# arduinoPlus.net
KiCad netlist of a schematic drawn in EAGLE
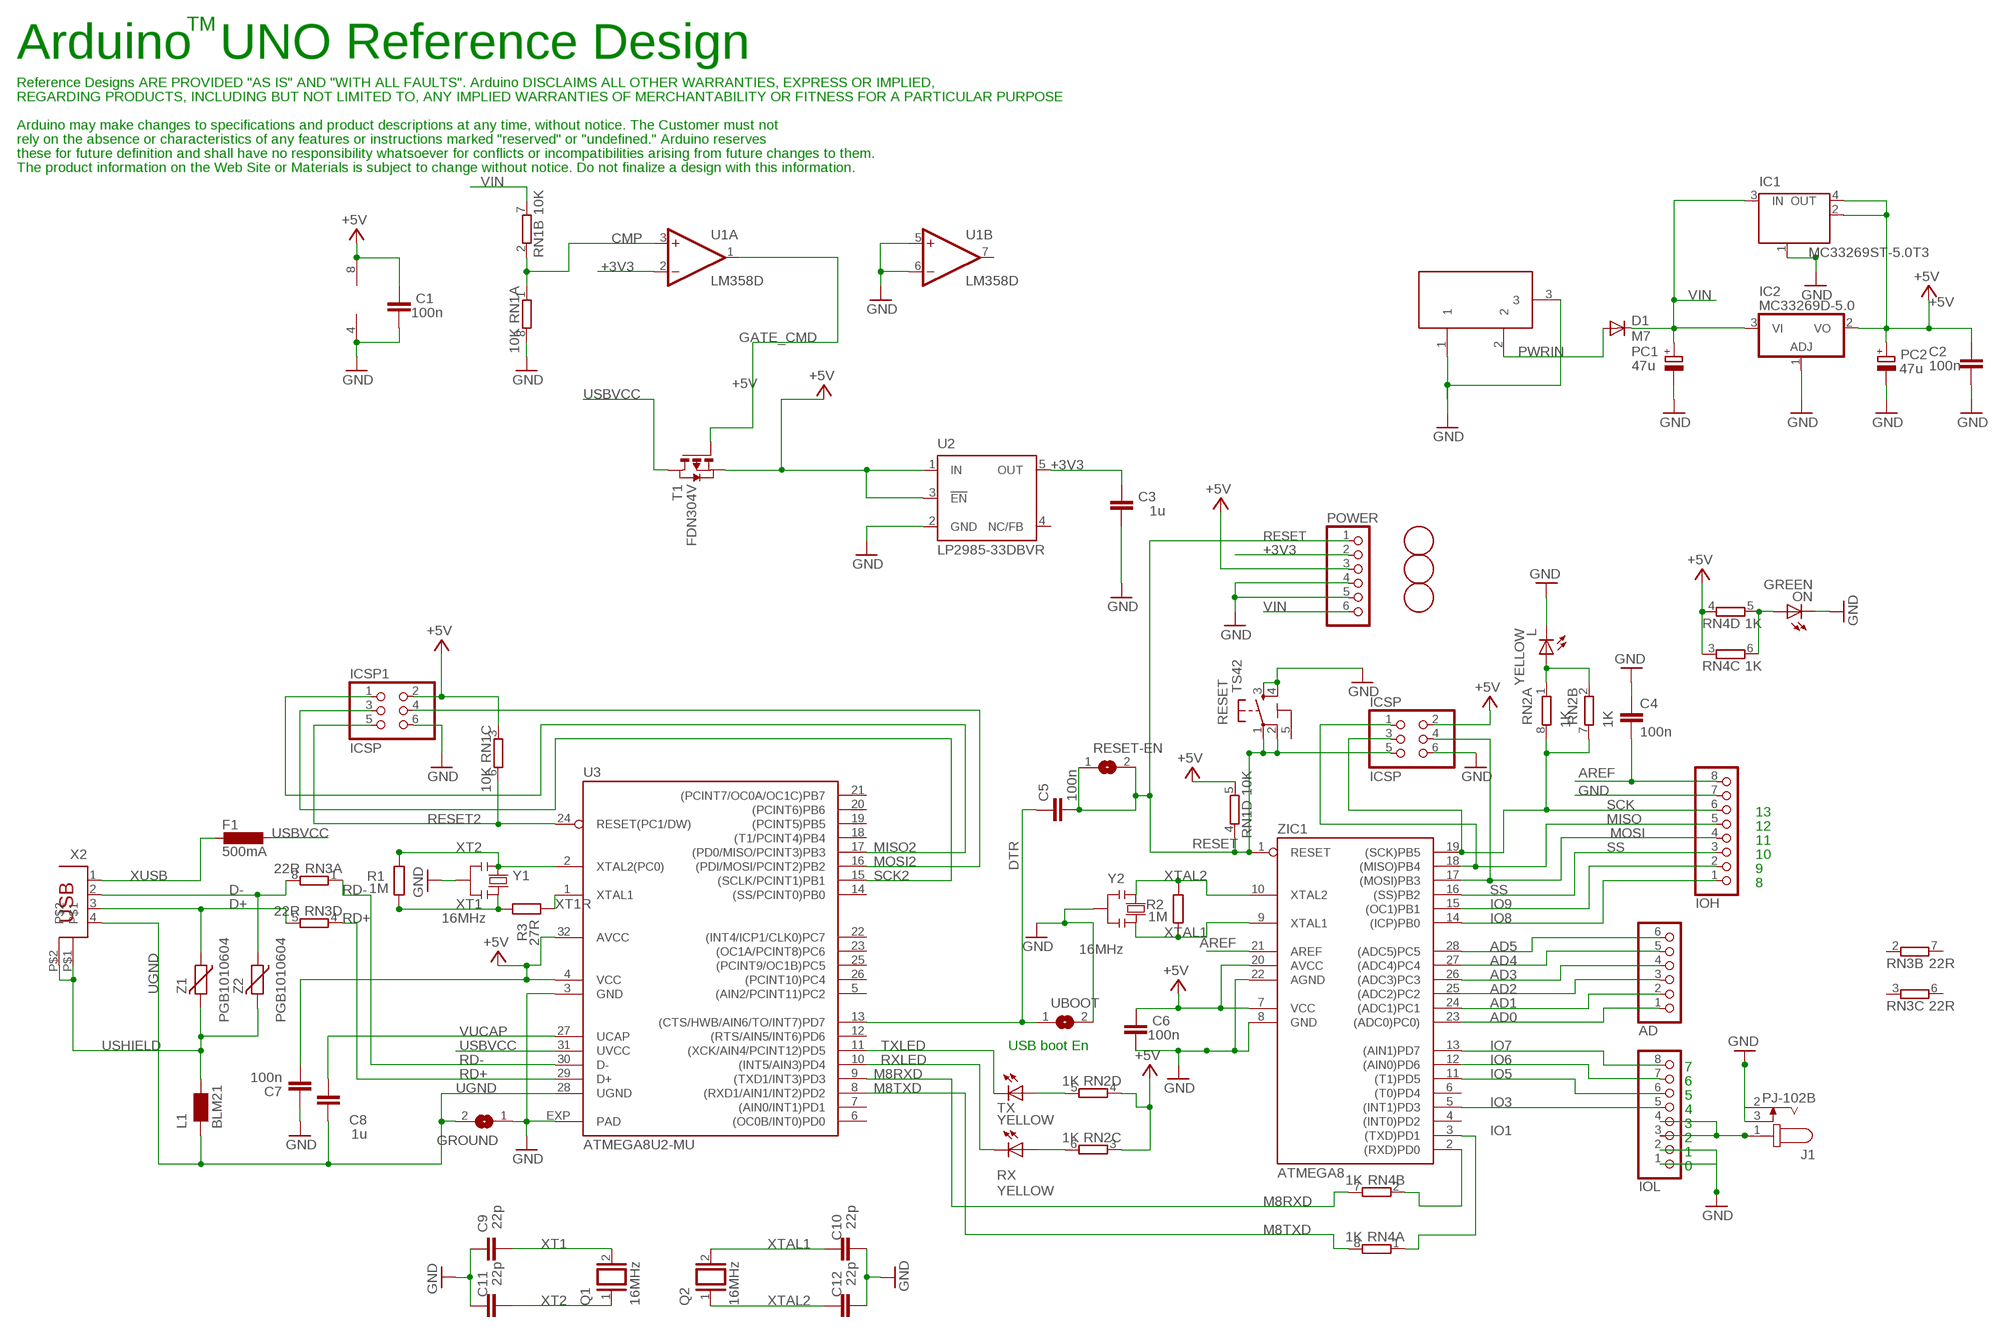
[diagram p0: schematic, sheet 1]

(export (version "E")
  (design (tool "Eeschema 10.0.6"))
  (components
    (comp (ref "AD")
      (value "PINHD-1X6")
      (footprint "eagle-import:1X06")
      (libsource (lib "eagle-import") (part "PINHD-1X6"))
    )
    (comp (ref "C1")
      (value "100n")
      (footprint "eagle-import:C0603-ROUND")
      (libsource (lib "eagle-import") (part "C-EU0603-RND"))
    )
    (comp (ref "C2")
      (value "100n")
      (footprint "eagle-import:C0603-ROUND")
      (libsource (lib "eagle-import") (part "C-EU0603-RND"))
    )
    (comp (ref "C3")
      (value "1u")
      (footprint "eagle-import:C0603-ROUND")
      (libsource (lib "eagle-import") (part "C-EU0603-RND"))
    )
    (comp (ref "C4")
      (value "100n")
      (footprint "eagle-import:C0603-ROUND")
      (libsource (lib "eagle-import") (part "C-EU0603-RND"))
    )
    (comp (ref "C5")
      (value "100n")
      (footprint "eagle-import:C0603-ROUND")
      (libsource (lib "eagle-import") (part "C-EU0603-RND"))
    )
    (comp (ref "C6")
      (value "100n")
      (footprint "eagle-import:C0603-ROUND")
      (libsource (lib "eagle-import") (part "C-EU0603-RND"))
    )
    (comp (ref "C7")
      (value "100n")
      (footprint "eagle-import:C0603-ROUND")
      (libsource (lib "eagle-import") (part "C-EU0603-RND"))
    )
    (comp (ref "C8")
      (value "1u")
      (footprint "eagle-import:C0603-ROUND")
      (libsource (lib "eagle-import") (part "C-EU0603-RND"))
    )
    (comp (ref "C9")
      (value "22p")
      (footprint "eagle-import:C0603-ROUND")
      (libsource (lib "eagle-import") (part "C-EU0603-RND"))
    )
    (comp (ref "C10")
      (value "22p")
      (footprint "eagle-import:C0603-ROUND")
      (libsource (lib "eagle-import") (part "C-EU0603-RND"))
    )
    (comp (ref "C11")
      (value "22p")
      (footprint "eagle-import:C0603-ROUND")
      (libsource (lib "eagle-import") (part "C-EU0603-RND"))
    )
    (comp (ref "C12")
      (value "22p")
      (footprint "eagle-import:C0603-ROUND")
      (libsource (lib "eagle-import") (part "C-EU0603-RND"))
    )
    (comp (ref "D1")
      (value "M7")
      (footprint "eagle-import:SMB")
      (libsource (lib "eagle-import") (part "DIODE-SMB"))
    )
    (comp (ref "F1")
      (value "500mA")
      (footprint "eagle-import:L1812")
      (libsource (lib "eagle-import") (part "L-EUL1812"))
    )
    (comp (ref "GROUND")
      (value "SJ")
      (footprint "eagle-import:SJ")
      (libsource (lib "eagle-import") (part "SJ"))
    )
    (comp (ref "IC1")
      (value "MC33269ST-5.0T3")
      (footprint "eagle-import:SOT223")
      (libsource (lib "eagle-import") (part "MC33269ST-3.3T3"))
    )
    (comp (ref "IC2")
      (value "MC33269D-5.0")
      (footprint "eagle-import:DPACK")
      (libsource (lib "eagle-import") (part "MC33269?D-5.0"))
    )
    (comp (ref "ICSP")
      (value "ICSP")
      (footprint "eagle-import:2X03")
      (libsource (lib "eagle-import") (part "PINHD-2X3"))
    )
    (comp (ref "ICSP1")
      (value "ICSP")
      (footprint "eagle-import:2X03")
      (libsource (lib "eagle-import") (part "PINHD-2X3"))
    )
    (comp (ref "IOH")
      (value "PINHD-1X8")
      (footprint "eagle-import:1X08")
      (libsource (lib "eagle-import") (part "PINHD-1X8"))
    )
    (comp (ref "IOL")
      (value "PINHD-1X8")
      (footprint "eagle-import:1X08")
      (libsource (lib "eagle-import") (part "PINHD-1X8"))
    )
    (comp (ref "J1")
      (value "PJ-102B")
      (footprint "eagle-import:CUI_PJ-102B")
      (fields (field (name "MF") "CUI Devices"))
      (libsource (lib "eagle-import") (part "PJ-102B"))
    )
    (comp (ref "L")
      (value "YELLOW")
      (footprint "eagle-import:CHIP-LED0805")
      (libsource (lib "eagle-import") (part "LEDCHIP-LED0805"))
    )
    (comp (ref "L1")
      (value "BLM21")
      (footprint "eagle-import:0805")
      (libsource (lib "eagle-import") (part "WE-CBF_0805"))
    )
    (comp (ref "ON")
      (value "GREEN")
      (footprint "eagle-import:CHIP-LED0805")
      (libsource (lib "eagle-import") (part "LEDCHIP-LED0805"))
    )
    (comp (ref "PC1")
      (value "47u")
      (footprint "eagle-import:PANASONIC_D")
      (libsource (lib "eagle-import") (part "CPOL-EUD"))
    )
    (comp (ref "PC2")
      (value "47u")
      (footprint "eagle-import:PANASONIC_D")
      (libsource (lib "eagle-import") (part "CPOL-EUD"))
    )
    (comp (ref "POWER")
      (value "PINHD-1X6")
      (footprint "eagle-import:1X06")
      (libsource (lib "eagle-import") (part "PINHD-1X6"))
    )
    (comp (ref "Q1")
      (value "16MHz")
      (footprint "eagle-import:QS")
      (libsource (lib "eagle-import") (part "XTAL/S"))
    )
    (comp (ref "Q2")
      (value "16MHz")
      (footprint "eagle-import:QS")
      (libsource (lib "eagle-import") (part "XTAL/S"))
    )
    (comp (ref "R1")
      (value "1M")
      (footprint "eagle-import:R0603-ROUND")
      (libsource (lib "eagle-import") (part "R-EU_R0603"))
    )
    (comp (ref "R2")
      (value "1M")
      (footprint "eagle-import:R0603-ROUND")
      (libsource (lib "eagle-import") (part "R-EU_R0603"))
    )
    (comp (ref "R3")
      (value "27R")
      (footprint "eagle-import:R0603-ROUND")
      (libsource (lib "eagle-import") (part "R-EU_R0603"))
    )
    (comp (ref "RESET")
      (value "TS42")
      (footprint "eagle-import:TS42")
      (libsource (lib "eagle-import") (part "TS42"))
    )
    (comp (ref "RESET-EN")
      (value "SJ")
      (footprint "eagle-import:SJ")
      (libsource (lib "eagle-import") (part "SJ"))
    )
    (comp (ref "RN1")
      (value "10K")
      (footprint "eagle-import:CAY16")
      (libsource (lib "eagle-import") (part "4R-NCAY16"))
    )
    (comp (ref "RN2")
      (value "1K")
      (footprint "eagle-import:CAY16")
      (libsource (lib "eagle-import") (part "4R-NCAY16"))
    )
    (comp (ref "RN3")
      (value "22R")
      (footprint "eagle-import:CAY16")
      (libsource (lib "eagle-import") (part "4R-NCAY16"))
    )
    (comp (ref "RN4")
      (value "1K")
      (footprint "eagle-import:CAY16")
      (libsource (lib "eagle-import") (part "4R-NCAY16"))
    )
    (comp (ref "RX")
      (value "YELLOW")
      (footprint "eagle-import:CHIP-LED0805")
      (libsource (lib "eagle-import") (part "LEDCHIP-LED0805"))
    )
    (comp (ref "T1")
      (value "FDN304V")
      (footprint "eagle-import:SOT-23")
      (libsource (lib "eagle-import") (part "PMOSSOT23"))
    )
    (comp (ref "TX")
      (value "YELLOW")
      (footprint "eagle-import:CHIP-LED0805")
      (libsource (lib "eagle-import") (part "LEDCHIP-LED0805"))
    )
    (comp (ref "U$3")
      (value "FIDUCIALMOUNT")
      (footprint "eagle-import:FIDUCIA-MOUNT")
      (libsource (lib "eagle-import") (part "FIDUCIALMOUNT"))
    )
    (comp (ref "U$4")
      (value "FIDUCIALMOUNT")
      (footprint "eagle-import:FIDUCIA-MOUNT")
      (libsource (lib "eagle-import") (part "FIDUCIALMOUNT"))
    )
    (comp (ref "U$6")
      (value "FIDUCIALMOUNT")
      (footprint "eagle-import:FIDUCIA-MOUNT")
      (libsource (lib "eagle-import") (part "FIDUCIALMOUNT"))
    )
    (comp (ref "U1")
      (value "LM358D")
      (footprint "eagle-import:SO08")
      (libsource (lib "eagle-import") (part "LM358D"))
    )
    (comp (ref "U2")
      (value "LP2985-33DBVR")
      (footprint "eagle-import:SOT23-DBV")
      (libsource (lib "eagle-import") (part "TPS77033"))
    )
    (comp (ref "U3")
      (value "ATMEGA8U2-MU")
      (footprint "eagle-import:QFN32")
      (libsource (lib "eagle-import") (part "ATMEGA8U2-MU"))
    )
    (comp (ref "UBOOT")
      (value "SJ")
      (footprint "eagle-import:SJ")
      (libsource (lib "eagle-import") (part "SJ"))
    )
    (comp (ref "X1")
      (value "DC21MMX")
      (footprint "eagle-import:DC-21MM")
      (libsource (lib "eagle-import") (part "DC21MMX"))
    )
    (comp (ref "X2")
      (value "PN61729")
      (footprint "eagle-import:PN61729")
      (libsource (lib "eagle-import") (part "PN61729"))
    )
    (comp (ref "Y1")
      (value "16MHz")
      (footprint "eagle-import:RESONATOR")
      (libsource (lib "eagle-import") (part "RESONATORMU"))
    )
    (comp (ref "Y2")
      (value "16MHz")
      (footprint "eagle-import:RESONATOR")
      (libsource (lib "eagle-import") (part "RESONATORMU"))
    )
    (comp (ref "Z1")
      (value "PGB1010604")
      (footprint "eagle-import:CT_CN0603")
      (libsource (lib "eagle-import") (part "VARISTORCN0603"))
    )
    (comp (ref "Z2")
      (value "PGB1010604")
      (footprint "eagle-import:CT_CN0603")
      (libsource (lib "eagle-import") (part "VARISTORCN0603"))
    )
    (comp (ref "ZIC1")
      (value "ATMEGA8")
      (footprint "eagle-import:DIL28-3")
      (libsource (lib "eagle-import") (part "AT90S4433P"))
    )
  )
  (nets
    (net (code "1") (name "+5V") (class "Default")
      (node (ref "C1") (pin "2") (pinfunction "2_2") (pintype "passive"))
      (node (ref "C2") (pin "2") (pinfunction "2_2") (pintype "passive"))
      (node (ref "C6") (pin "2") (pinfunction "2_2") (pintype "passive"))
      (node (ref "C7") (pin "1") (pinfunction "1_1") (pintype "passive"))
      (node (ref "IC1") (pin "2") (pinfunction "OUT_2") (pintype "passive"))
      (node (ref "IC1") (pin "4") (pinfunction "OUT_4") (pintype "passive"))
      (node (ref "IC2") (pin "2") (pinfunction "VO_2") (pintype "passive"))
      (node (ref "ICSP") (pin "2") (pinfunction "2_2") (pintype "passive"))
      (node (ref "ICSP1") (pin "2") (pinfunction "2_2") (pintype "passive"))
      (node (ref "PC2") (pin "+") (pinfunction "+_+") (pintype "passive"))
      (node (ref "POWER") (pin "3") (pinfunction "3_3") (pintype "passive"))
      (node (ref "RN1") (pin "3") (pinfunction "1_3") (pintype "passive"))
      (node (ref "RN1") (pin "5") (pinfunction "2_5") (pintype "passive"))
      (node (ref "RN2") (pin "3") (pinfunction "1_3") (pintype "passive"))
      (node (ref "RN2") (pin "4") (pinfunction "1_4") (pintype "passive"))
      (node (ref "RN4") (pin "3") (pinfunction "1_3") (pintype "passive"))
      (node (ref "RN4") (pin "4") (pinfunction "1_4") (pintype "passive"))
      (node (ref "T1") (pin "2") (pinfunction "S_2") (pintype "passive"))
      (node (ref "U1") (pin "8") (pinfunction "V+_8") (pintype "power_in"))
      (node (ref "U2") (pin "1") (pinfunction "IN_1") (pintype "input"))
      (node (ref "U2") (pin "3") (pinfunction "~{EN}_3") (pintype "input"))
      (node (ref "U3") (pin "32") (pinfunction "AVCC_32") (pintype "power_in"))
      (node (ref "U3") (pin "4") (pinfunction "VCC_4") (pintype "power_in"))
      (node (ref "ZIC1") (pin "20") (pinfunction "AVCC_20") (pintype "power_in"))
      (node (ref "ZIC1") (pin "7") (pinfunction "VCC_7") (pintype "power_in"))
    )
    (net (code "2") (name "/+3V3") (class "Default")
      (node (ref "C3") (pin "2") (pinfunction "2_2") (pintype "passive"))
      (node (ref "POWER") (pin "2") (pinfunction "2_2") (pintype "passive"))
      (node (ref "U1") (pin "2") (pinfunction "-IN_2") (pintype "input"))
      (node (ref "U2") (pin "5") (pinfunction "OUT_5") (pintype "passive"))
    )
    (net (code "3") (name "/5-GND") (class "Default")
      (node (ref "RESET") (pin "5") (pinfunction "5-GND_5") (pintype "power_in"))
    )
    (net (code "4") (name "/AD0") (class "Default")
      (node (ref "AD") (pin "1") (pinfunction "1_1") (pintype "passive"))
      (node (ref "ZIC1") (pin "23") (pinfunction "(ADC0)PC0)_23") (pintype "bidirectional"))
    )
    (net (code "5") (name "/AD1") (class "Default")
      (node (ref "AD") (pin "2") (pinfunction "2_2") (pintype "passive"))
      (node (ref "ZIC1") (pin "24") (pinfunction "(ADC1)PC1_24") (pintype "bidirectional"))
    )
    (net (code "6") (name "/AD2") (class "Default")
      (node (ref "AD") (pin "3") (pinfunction "3_3") (pintype "passive"))
      (node (ref "ZIC1") (pin "25") (pinfunction "(ADC2)PC2_25") (pintype "bidirectional"))
    )
    (net (code "7") (name "/AD3") (class "Default")
      (node (ref "AD") (pin "4") (pinfunction "4_4") (pintype "passive"))
      (node (ref "ZIC1") (pin "26") (pinfunction "(ADC3)PC3_26") (pintype "bidirectional"))
    )
    (net (code "8") (name "/AD4") (class "Default")
      (node (ref "AD") (pin "5") (pinfunction "5_5") (pintype "passive"))
      (node (ref "ZIC1") (pin "27") (pinfunction "(ADC4)PC4_27") (pintype "bidirectional"))
    )
    (net (code "9") (name "/AD5") (class "Default")
      (node (ref "AD") (pin "6") (pinfunction "6_6") (pintype "passive"))
      (node (ref "ZIC1") (pin "28") (pinfunction "(ADC5)PC5_28") (pintype "bidirectional"))
    )
    (net (code "10") (name "/AREF") (class "Default")
      (node (ref "C4") (pin "2") (pinfunction "2_2") (pintype "passive"))
      (node (ref "IOH") (pin "8") (pinfunction "8_8") (pintype "passive"))
      (node (ref "ZIC1") (pin "21") (pinfunction "AREF_21") (pintype "passive"))
    )
    (net (code "11") (name "/CMP") (class "Default")
      (node (ref "RN1") (pin "1") (pinfunction "1_1") (pintype "passive"))
      (node (ref "RN1") (pin "2") (pinfunction "1_2") (pintype "passive"))
      (node (ref "U1") (pin "3") (pinfunction "+IN_3") (pintype "input"))
    )
    (net (code "12") (name "/D+") (class "Default")
      (node (ref "RN3") (pin "5") (pinfunction "2_5") (pintype "passive"))
      (node (ref "X2") (pin "3") (pinfunction "3_3") (pintype "bidirectional"))
      (node (ref "Z1") (pin "1") (pinfunction "1_1") (pintype "passive"))
    )
    (net (code "13") (name "/D-") (class "Default")
      (node (ref "RN3") (pin "8") (pinfunction "2_8") (pintype "passive"))
      (node (ref "X2") (pin "2") (pinfunction "2_2") (pintype "bidirectional"))
      (node (ref "Z2") (pin "1") (pinfunction "1_1") (pintype "passive"))
    )
    (net (code "14") (name "/DTR") (class "Default")
      (node (ref "C5") (pin "1") (pinfunction "1_1") (pintype "passive"))
      (node (ref "U3") (pin "13") (pinfunction "(CTS/HWB/AIN6/TO/INT7)PD7_13") (pintype "bidirectional"))
      (node (ref "UBOOT") (pin "1") (pinfunction "1_1") (pintype "passive"))
    )
    (net (code "15") (name "/GATE_CMD") (class "Default")
      (node (ref "T1") (pin "3") (pinfunction "G_3") (pintype "passive"))
      (node (ref "U1") (pin "1") (pinfunction "OUT_1") (pintype "output"))
    )
    (net (code "16") (name "/IO1") (class "Default")
      (node (ref "RN4") (pin "1") (pinfunction "1_1") (pintype "passive"))
      (node (ref "ZIC1") (pin "3") (pinfunction "(TXD)PD1_3") (pintype "bidirectional"))
    )
    (net (code "17") (name "/IO3") (class "Default")
      (node (ref "IOL") (pin "5") (pinfunction "5_5") (pintype "passive"))
      (node (ref "ZIC1") (pin "5") (pinfunction "(INT1)PD3_5") (pintype "bidirectional"))
    )
    (net (code "18") (name "/IO5") (class "Default")
      (node (ref "IOL") (pin "6") (pinfunction "6_6") (pintype "passive"))
      (node (ref "ZIC1") (pin "11") (pinfunction "(T1)PD5_11") (pintype "bidirectional"))
    )
    (net (code "19") (name "/IO6") (class "Default")
      (node (ref "IOL") (pin "7") (pinfunction "7_7") (pintype "passive"))
      (node (ref "ZIC1") (pin "12") (pinfunction "(AIN0)PD6_12") (pintype "bidirectional"))
    )
    (net (code "20") (name "/IO7") (class "Default")
      (node (ref "IOL") (pin "8") (pinfunction "8_8") (pintype "passive"))
      (node (ref "ZIC1") (pin "13") (pinfunction "(AIN1)PD7_13") (pintype "bidirectional"))
    )
    (net (code "21") (name "/IO8") (class "Default")
      (node (ref "IOH") (pin "1") (pinfunction "1_1") (pintype "passive"))
      (node (ref "ZIC1") (pin "14") (pinfunction "(ICP)PB0_14") (pintype "bidirectional"))
    )
    (net (code "22") (name "/IO9") (class "Default")
      (node (ref "IOH") (pin "2") (pinfunction "2_2") (pintype "passive"))
      (node (ref "ZIC1") (pin "15") (pinfunction "(OC1)PB1_15") (pintype "bidirectional"))
    )
    (net (code "23") (name "/M8RXD") (class "Default")
      (node (ref "RN4") (pin "7") (pinfunction "2_7") (pintype "passive"))
      (node (ref "U3") (pin "9") (pinfunction "(TXD1/INT3)PD3_9") (pintype "bidirectional"))
    )
    (net (code "24") (name "/M8TXD") (class "Default")
      (node (ref "RN4") (pin "8") (pinfunction "2_8") (pintype "passive"))
      (node (ref "U3") (pin "8") (pinfunction "(RXD1/AIN1/INT2)PD2_8") (pintype "bidirectional"))
    )
    (net (code "25") (name "/MISO") (class "Default")
      (node (ref "ICSP") (pin "1") (pinfunction "1_1") (pintype "passive"))
      (node (ref "IOH") (pin "5") (pinfunction "5_5") (pintype "passive"))
      (node (ref "ZIC1") (pin "18") (pinfunction "(MISO)PB4_18") (pintype "bidirectional"))
    )
    (net (code "26") (name "/MISO2") (class "Default")
      (node (ref "ICSP1") (pin "1") (pinfunction "1_1") (pintype "passive"))
      (node (ref "U3") (pin "17") (pinfunction "(PD0/MISO/PCINT3)PB3_17") (pintype "bidirectional"))
    )
    (net (code "27") (name "/MOSI") (class "Default")
      (node (ref "ICSP") (pin "4") (pinfunction "4_4") (pintype "passive"))
      (node (ref "IOH") (pin "4") (pinfunction "4_4") (pintype "passive"))
      (node (ref "ZIC1") (pin "17") (pinfunction "(MOSI)PB3_17") (pintype "bidirectional"))
    )
    (net (code "28") (name "/MOSI2") (class "Default")
      (node (ref "ICSP1") (pin "4") (pinfunction "4_4") (pintype "passive"))
      (node (ref "U3") (pin "16") (pinfunction "(PDI/MOSI/PCINT2)PB2_16") (pintype "bidirectional"))
    )
    (net (code "29") (name "/PWRIN") (class "Default")
      (node (ref "D1") (pin "A") (pinfunction "A_A") (pintype "passive"))
      (node (ref "X1") (pin "2") (pinfunction "2_2") (pintype "power_in"))
    )
    (net (code "30") (name "/RD+") (class "Default")
      (node (ref "RN3") (pin "4") (pinfunction "1_4") (pintype "passive"))
      (node (ref "U3") (pin "29") (pinfunction "D+_29") (pintype "bidirectional"))
    )
    (net (code "31") (name "/RD-") (class "Default")
      (node (ref "RN3") (pin "1") (pinfunction "1_1") (pintype "passive"))
      (node (ref "U3") (pin "30") (pinfunction "D-_30") (pintype "bidirectional"))
    )
    (net (code "32") (name "/RESET") (class "Default")
      (node (ref "C5") (pin "2") (pinfunction "2_2") (pintype "passive"))
      (node (ref "ICSP") (pin "5") (pinfunction "5_5") (pintype "passive"))
      (node (ref "POWER") (pin "1") (pinfunction "1_1") (pintype "passive"))
      (node (ref "RESET") (pin "1") (pinfunction "1_1") (pintype "passive"))
      (node (ref "RESET") (pin "2") (pinfunction "2_2") (pintype "passive"))
      (node (ref "RESET-EN") (pin "1") (pinfunction "1_1") (pintype "passive"))
      (node (ref "RESET-EN") (pin "2") (pinfunction "2_2") (pintype "passive"))
      (node (ref "RN1") (pin "4") (pinfunction "1_4") (pintype "passive"))
      (node (ref "ZIC1") (pin "1") (pinfunction "RESET_1") (pintype "input"))
    )
    (net (code "33") (name "/RESET2") (class "Default")
      (node (ref "ICSP1") (pin "5") (pinfunction "5_5") (pintype "passive"))
      (node (ref "RN1") (pin "6") (pinfunction "2_6") (pintype "passive"))
      (node (ref "U3") (pin "24") (pinfunction "RESET(PC1/DW)_24") (pintype "input"))
    )
    (net (code "34") (name "/RXLED") (class "Default")
      (node (ref "RX") (pin "C") (pinfunction "C_C") (pintype "passive"))
      (node (ref "U3") (pin "10") (pinfunction "(INT5/AIN3)PD4_10") (pintype "bidirectional"))
    )
    (net (code "35") (name "/SCK") (class "Default")
      (node (ref "ICSP") (pin "3") (pinfunction "3_3") (pintype "passive"))
      (node (ref "IOH") (pin "6") (pinfunction "6_6") (pintype "passive"))
      (node (ref "RN2") (pin "7") (pinfunction "2_7") (pintype "passive"))
      (node (ref "RN2") (pin "8") (pinfunction "2_8") (pintype "passive"))
      (node (ref "ZIC1") (pin "19") (pinfunction "(SCK)PB5_19") (pintype "bidirectional"))
    )
    (net (code "36") (name "/SCK2") (class "Default")
      (node (ref "ICSP1") (pin "3") (pinfunction "3_3") (pintype "passive"))
      (node (ref "U3") (pin "15") (pinfunction "(SCLK/PCINT1)PB1_15") (pintype "bidirectional"))
    )
    (net (code "37") (name "/SS") (class "Default")
      (node (ref "IOH") (pin "3") (pinfunction "3_3") (pintype "passive"))
      (node (ref "ZIC1") (pin "16") (pinfunction "(SS)PB2_16") (pintype "bidirectional"))
    )
    (net (code "38") (name "/TXLED") (class "Default")
      (node (ref "TX") (pin "C") (pinfunction "C_C") (pintype "passive"))
      (node (ref "U3") (pin "11") (pinfunction "(XCK/AIN4/PCINT12)PD5_11") (pintype "bidirectional"))
    )
    (net (code "39") (name "/UGND") (class "Default")
      (node (ref "C8") (pin "2") (pinfunction "2_2") (pintype "passive"))
      (node (ref "GROUND") (pin "2") (pinfunction "2_2") (pintype "passive"))
      (node (ref "L1") (pin "1") (pinfunction "1_1") (pintype "passive"))
      (node (ref "U3") (pin "28") (pinfunction "UGND_28") (pintype "power_in"))
      (node (ref "X2") (pin "4") (pinfunction "4_4") (pintype "bidirectional"))
    )
    (net (code "40") (name "/USBVCC") (class "Default")
      (node (ref "F1") (pin "1") (pinfunction "1_1") (pintype "passive"))
      (node (ref "T1") (pin "1") (pinfunction "D_1") (pintype "passive"))
      (node (ref "U3") (pin "31") (pinfunction "UVCC_31") (pintype "power_in"))
    )
    (net (code "41") (name "/USHIELD") (class "Default")
      (node (ref "L1") (pin "2") (pinfunction "2_2") (pintype "passive"))
      (node (ref "X2") (pin "P$1") (pinfunction "P$1_P$1") (pintype "bidirectional"))
      (node (ref "X2") (pin "P$2") (pinfunction "P$2_P$2") (pintype "bidirectional"))
      (node (ref "Z1") (pin "2") (pinfunction "2_2") (pintype "passive"))
      (node (ref "Z2") (pin "2") (pinfunction "2_2") (pintype "passive"))
    )
    (net (code "42") (name "/VIN") (class "Default")
      (node (ref "D1") (pin "C") (pinfunction "C_C") (pintype "passive"))
      (node (ref "IC1") (pin "3") (pinfunction "IN_3") (pintype "input"))
      (node (ref "IC2") (pin "3") (pinfunction "VI_3") (pintype "input"))
      (node (ref "PC1") (pin "+") (pinfunction "+_+") (pintype "passive"))
      (node (ref "POWER") (pin "6") (pinfunction "6_6") (pintype "passive"))
      (node (ref "RN1") (pin "7") (pinfunction "2_7") (pintype "passive"))
    )
    (net (code "43") (name "/VUCAP") (class "Default")
      (node (ref "C8") (pin "1") (pinfunction "1_1") (pintype "passive"))
      (node (ref "U3") (pin "27") (pinfunction "UCAP_27") (pintype "passive"))
    )
    (net (code "44") (name "/XT1") (class "Default")
      (node (ref "C9") (pin "1") (pinfunction "1_1") (pintype "passive"))
      (node (ref "Q1") (pin "2") (pinfunction "2_2") (pintype "passive"))
      (node (ref "R1") (pin "1") (pinfunction "1_1") (pintype "passive"))
      (node (ref "R3") (pin "2") (pinfunction "2_2") (pintype "passive"))
      (node (ref "Y1") (pin "3") (pinfunction "3_3") (pintype "passive"))
    )
    (net (code "45") (name "/XT1R") (class "Default")
      (node (ref "R3") (pin "1") (pinfunction "1_1") (pintype "passive"))
      (node (ref "U3") (pin "1") (pinfunction "XTAL1_1") (pintype "bidirectional"))
    )
    (net (code "46") (name "/XT2") (class "Default")
      (node (ref "C11") (pin "1") (pinfunction "1_1") (pintype "passive"))
      (node (ref "Q1") (pin "1") (pinfunction "1_1") (pintype "passive"))
      (node (ref "R1") (pin "2") (pinfunction "2_2") (pintype "passive"))
      (node (ref "U3") (pin "2") (pinfunction "XTAL2(PC0)_2") (pintype "bidirectional"))
      (node (ref "Y1") (pin "1") (pinfunction "1_1") (pintype "passive"))
    )
    (net (code "47") (name "/XTAL1") (class "Default")
      (node (ref "C10") (pin "2") (pinfunction "2_2") (pintype "passive"))
      (node (ref "Q2") (pin "2") (pinfunction "2_2") (pintype "passive"))
      (node (ref "R2") (pin "1") (pinfunction "1_1") (pintype "passive"))
      (node (ref "Y2") (pin "3") (pinfunction "3_3") (pintype "passive"))
      (node (ref "ZIC1") (pin "9") (pinfunction "XTAL1_9") (pintype "bidirectional"))
    )
    (net (code "48") (name "/XTAL2") (class "Default")
      (node (ref "C12") (pin "2") (pinfunction "2_2") (pintype "passive"))
      (node (ref "Q2") (pin "1") (pinfunction "1_1") (pintype "passive"))
      (node (ref "R2") (pin "2") (pinfunction "2_2") (pintype "passive"))
      (node (ref "Y2") (pin "1") (pinfunction "1_1") (pintype "passive"))
      (node (ref "ZIC1") (pin "10") (pinfunction "XTAL2_10") (pintype "bidirectional"))
    )
    (net (code "49") (name "/XUSB") (class "Default")
      (node (ref "F1") (pin "2") (pinfunction "2_2") (pintype "passive"))
      (node (ref "X2") (pin "1") (pinfunction "1_1") (pintype "bidirectional"))
    )
    (net (code "50") (name "GND") (class "Default")
      (node (ref "C1") (pin "1") (pinfunction "1_1") (pintype "passive"))
      (node (ref "C10") (pin "1") (pinfunction "1_1") (pintype "passive"))
      (node (ref "C11") (pin "2") (pinfunction "2_2") (pintype "passive"))
      (node (ref "C12") (pin "1") (pinfunction "1_1") (pintype "passive"))
      (node (ref "C2") (pin "1") (pinfunction "1_1") (pintype "passive"))
      (node (ref "C3") (pin "1") (pinfunction "1_1") (pintype "passive"))
      (node (ref "C4") (pin "1") (pinfunction "1_1") (pintype "passive"))
      (node (ref "C6") (pin "1") (pinfunction "1_1") (pintype "passive"))
      (node (ref "C7") (pin "2") (pinfunction "2_2") (pintype "passive"))
      (node (ref "C9") (pin "2") (pinfunction "2_2") (pintype "passive"))
      (node (ref "GROUND") (pin "1") (pinfunction "1_1") (pintype "passive"))
      (node (ref "IC1") (pin "1") (pinfunction "GND/ADJ_1") (pintype "input"))
      (node (ref "IC2") (pin "1") (pinfunction "ADJ_1") (pintype "input"))
      (node (ref "ICSP") (pin "6") (pinfunction "6_6") (pintype "passive"))
      (node (ref "ICSP1") (pin "6") (pinfunction "6_6") (pintype "passive"))
      (node (ref "IOH") (pin "7") (pinfunction "7_7") (pintype "passive"))
      (node (ref "IOL") (pin "1") (pinfunction "1_1") (pintype "passive"))
      (node (ref "IOL") (pin "2") (pinfunction "2_2") (pintype "passive"))
      (node (ref "J1") (pin "2") (pinfunction "2_2") (pintype "passive"))
      (node (ref "J1") (pin "3") (pinfunction "3_3") (pintype "passive"))
      (node (ref "L") (pin "C") (pinfunction "C_C") (pintype "passive"))
      (node (ref "ON") (pin "C") (pinfunction "C_C") (pintype "passive"))
      (node (ref "PC1") (pin "-") (pinfunction "-_-") (pintype "passive"))
      (node (ref "PC2") (pin "-") (pinfunction "-_-") (pintype "passive"))
      (node (ref "POWER") (pin "4") (pinfunction "4_4") (pintype "passive"))
      (node (ref "POWER") (pin "5") (pinfunction "5_5") (pintype "passive"))
      (node (ref "RESET") (pin "3") (pinfunction "3_3") (pintype "passive"))
      (node (ref "RESET") (pin "4") (pinfunction "4_4") (pintype "passive"))
      (node (ref "RN1") (pin "8") (pinfunction "2_8") (pintype "passive"))
      (node (ref "U1") (pin "4") (pinfunction "V-_4") (pintype "power_in"))
      (node (ref "U1") (pin "5") (pinfunction "+IN_5") (pintype "input"))
      (node (ref "U1") (pin "6") (pinfunction "-IN_6") (pintype "input"))
      (node (ref "U2") (pin "2") (pinfunction "GND_2") (pintype "power_in"))
      (node (ref "U3") (pin "3") (pinfunction "GND_3") (pintype "power_in"))
      (node (ref "U3") (pin "EXP") (pinfunction "PAD_EXP") (pintype "power_in"))
      (node (ref "UBOOT") (pin "2") (pinfunction "2_2") (pintype "passive"))
      (node (ref "X1") (pin "1") (pinfunction "1_1") (pintype "power_in"))
      (node (ref "X1") (pin "3") (pinfunction "3_3") (pintype "power_in"))
      (node (ref "Y1") (pin "2") (pinfunction "2_2") (pintype "passive"))
      (node (ref "Y2") (pin "2") (pinfunction "2_2") (pintype "passive"))
      (node (ref "ZIC1") (pin "22") (pinfunction "AGND_22") (pintype "power_in"))
      (node (ref "ZIC1") (pin "8") (pinfunction "GND_8") (pintype "power_in"))
    )
    (net (code "51") (name "Net-(IOL-Pad3)") (class "Default")
      (node (ref "IOL") (pin "3") (pinfunction "3_3") (pintype "passive"))
      (node (ref "IOL") (pin "4") (pinfunction "4_4") (pintype "passive"))
      (node (ref "J1") (pin "1") (pinfunction "1_1") (pintype "passive"))
    )
    (net (code "52") (name "Net-(RN2B-1)") (class "Default")
      (node (ref "L") (pin "A") (pinfunction "A_A") (pintype "passive"))
      (node (ref "RN2") (pin "1") (pinfunction "1_1") (pintype "passive"))
      (node (ref "RN2") (pin "2") (pinfunction "1_2") (pintype "passive"))
    )
    (net (code "53") (name "Net-(RN2C-2)") (class "Default")
      (node (ref "RN2") (pin "6") (pinfunction "2_6") (pintype "passive"))
      (node (ref "RX") (pin "A") (pinfunction "A_A") (pintype "passive"))
    )
    (net (code "54") (name "Net-(RN2D-2)") (class "Default")
      (node (ref "RN2") (pin "5") (pinfunction "2_5") (pintype "passive"))
      (node (ref "TX") (pin "A") (pinfunction "A_A") (pintype "passive"))
    )
    (net (code "55") (name "Net-(RN4B-1)") (class "Default")
      (node (ref "RN4") (pin "2") (pinfunction "1_2") (pintype "passive"))
      (node (ref "ZIC1") (pin "2") (pinfunction "(RXD)PD0_2") (pintype "bidirectional"))
    )
    (net (code "56") (name "Net-(RN4C-2)") (class "Default")
      (node (ref "ON") (pin "A") (pinfunction "A_A") (pintype "passive"))
      (node (ref "RN4") (pin "5") (pinfunction "2_5") (pintype "passive"))
      (node (ref "RN4") (pin "6") (pinfunction "2_6") (pintype "passive"))
    )
    (net (code "57") (name "unconnected-(RN3B-1-Pad2)") (class "Default")
      (node (ref "RN3") (pin "2") (pinfunction "1_2") (pintype "passive"))
    )
    (net (code "58") (name "unconnected-(RN3B-2-Pad7)") (class "Default")
      (node (ref "RN3") (pin "7") (pinfunction "2_7") (pintype "passive"))
    )
    (net (code "59") (name "unconnected-(RN3C-1-Pad3)") (class "Default")
      (node (ref "RN3") (pin "3") (pinfunction "1_3") (pintype "passive"))
    )
    (net (code "60") (name "unconnected-(RN3C-2-Pad6)") (class "Default")
      (node (ref "RN3") (pin "6") (pinfunction "2_6") (pintype "passive"))
    )
    (net (code "61") (name "unconnected-(U1B-OUT-Pad7)") (class "Default")
      (node (ref "U1") (pin "7") (pinfunction "OUT_7") (pintype "output"))
    )
    (net (code "62") (name "unconnected-(U2-NC{slash}FB-Pad4)") (class "Default")
      (node (ref "U2") (pin "4") (pinfunction "NC/FB_4") (pintype "passive"))
    )
    (net (code "63") (name "unconnected-(U3-(AIN0{slash}INT1)PD1-Pad7)") (class "Default")
      (node (ref "U3") (pin "7") (pinfunction "(AIN0/INT1)PD1_7") (pintype "bidirectional"))
    )
    (net (code "64") (name "unconnected-(U3-(AIN2{slash}PCINT11)PC2-Pad5)") (class "Default")
      (node (ref "U3") (pin "5") (pinfunction "(AIN2/PCINT11)PC2_5") (pintype "bidirectional"))
    )
    (net (code "65") (name "unconnected-(U3-(INT4{slash}ICP1{slash}CLK0)PC7-Pad22)") (class "Default")
      (node (ref "U3") (pin "22") (pinfunction "(INT4/ICP1/CLK0)PC7_22") (pintype "bidirectional"))
    )
    (net (code "66") (name "unconnected-(U3-(OC0B{slash}INT0)PD0-Pad6)") (class "Default")
      (node (ref "U3") (pin "6") (pinfunction "(OC0B/INT0)PD0_6") (pintype "bidirectional"))
    )
    (net (code "67") (name "unconnected-(U3-(OC1A{slash}PCINT8)PC6-Pad23)") (class "Default")
      (node (ref "U3") (pin "23") (pinfunction "(OC1A/PCINT8)PC6_23") (pintype "bidirectional"))
    )
    (net (code "68") (name "unconnected-(U3-(PCINT5)PB5-Pad19)") (class "Default")
      (node (ref "U3") (pin "19") (pinfunction "(PCINT5)PB5_19") (pintype "bidirectional"))
    )
    (net (code "69") (name "unconnected-(U3-(PCINT6)PB6-Pad20)") (class "Default")
      (node (ref "U3") (pin "20") (pinfunction "(PCINT6)PB6_20") (pintype "bidirectional"))
    )
    (net (code "70") (name "unconnected-(U3-(PCINT7{slash}OC0A{slash}OC1C)PB7-Pad21)") (class "Default")
      (node (ref "U3") (pin "21") (pinfunction "(PCINT7/OC0A/OC1C)PB7_21") (pintype "bidirectional"))
    )
    (net (code "71") (name "unconnected-(U3-(PCINT9{slash}OC1B)PC5-Pad25)") (class "Default")
      (node (ref "U3") (pin "25") (pinfunction "(PCINT9/OC1B)PC5_25") (pintype "bidirectional"))
    )
    (net (code "72") (name "unconnected-(U3-(PCINT10)PC4-Pad26)") (class "Default")
      (node (ref "U3") (pin "26") (pinfunction "(PCINT10)PC4_26") (pintype "bidirectional"))
    )
    (net (code "73") (name "unconnected-(U3-(RTS{slash}AIN5{slash}INT6)PD6-Pad12)") (class "Default")
      (node (ref "U3") (pin "12") (pinfunction "(RTS/AIN5/INT6)PD6_12") (pintype "bidirectional"))
    )
    (net (code "74") (name "unconnected-(U3-(SS{slash}PCINT0)PB0-Pad14)") (class "Default")
      (node (ref "U3") (pin "14") (pinfunction "(SS/PCINT0)PB0_14") (pintype "bidirectional"))
    )
    (net (code "75") (name "unconnected-(U3-(T1{slash}PCINT4)PB4-Pad18)") (class "Default")
      (node (ref "U3") (pin "18") (pinfunction "(T1/PCINT4)PB4_18") (pintype "bidirectional"))
    )
    (net (code "76") (name "unconnected-(ZIC1-(INT0)PD2-Pad4)") (class "Default")
      (node (ref "ZIC1") (pin "4") (pinfunction "(INT0)PD2_4") (pintype "bidirectional"))
    )
    (net (code "77") (name "unconnected-(ZIC1-(T0)PD4-Pad6)") (class "Default")
      (node (ref "ZIC1") (pin "6") (pinfunction "(T0)PD4_6") (pintype "bidirectional"))
    )
  )
)
